# LSS_Pro_V0_2_BOTTOM.net
KiCad netlist of a schematic drawn in EAGLE
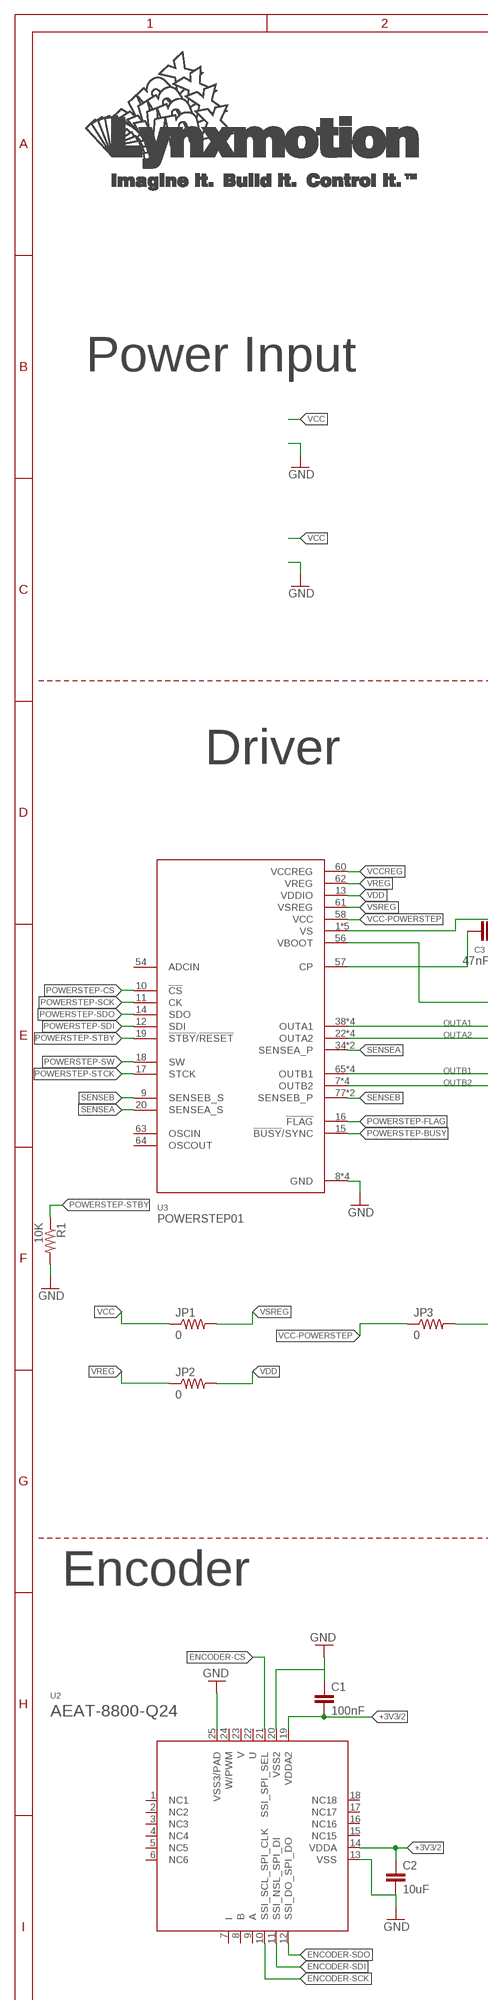
[diagram p0: schematic, sheet 1, part 1 of 2]
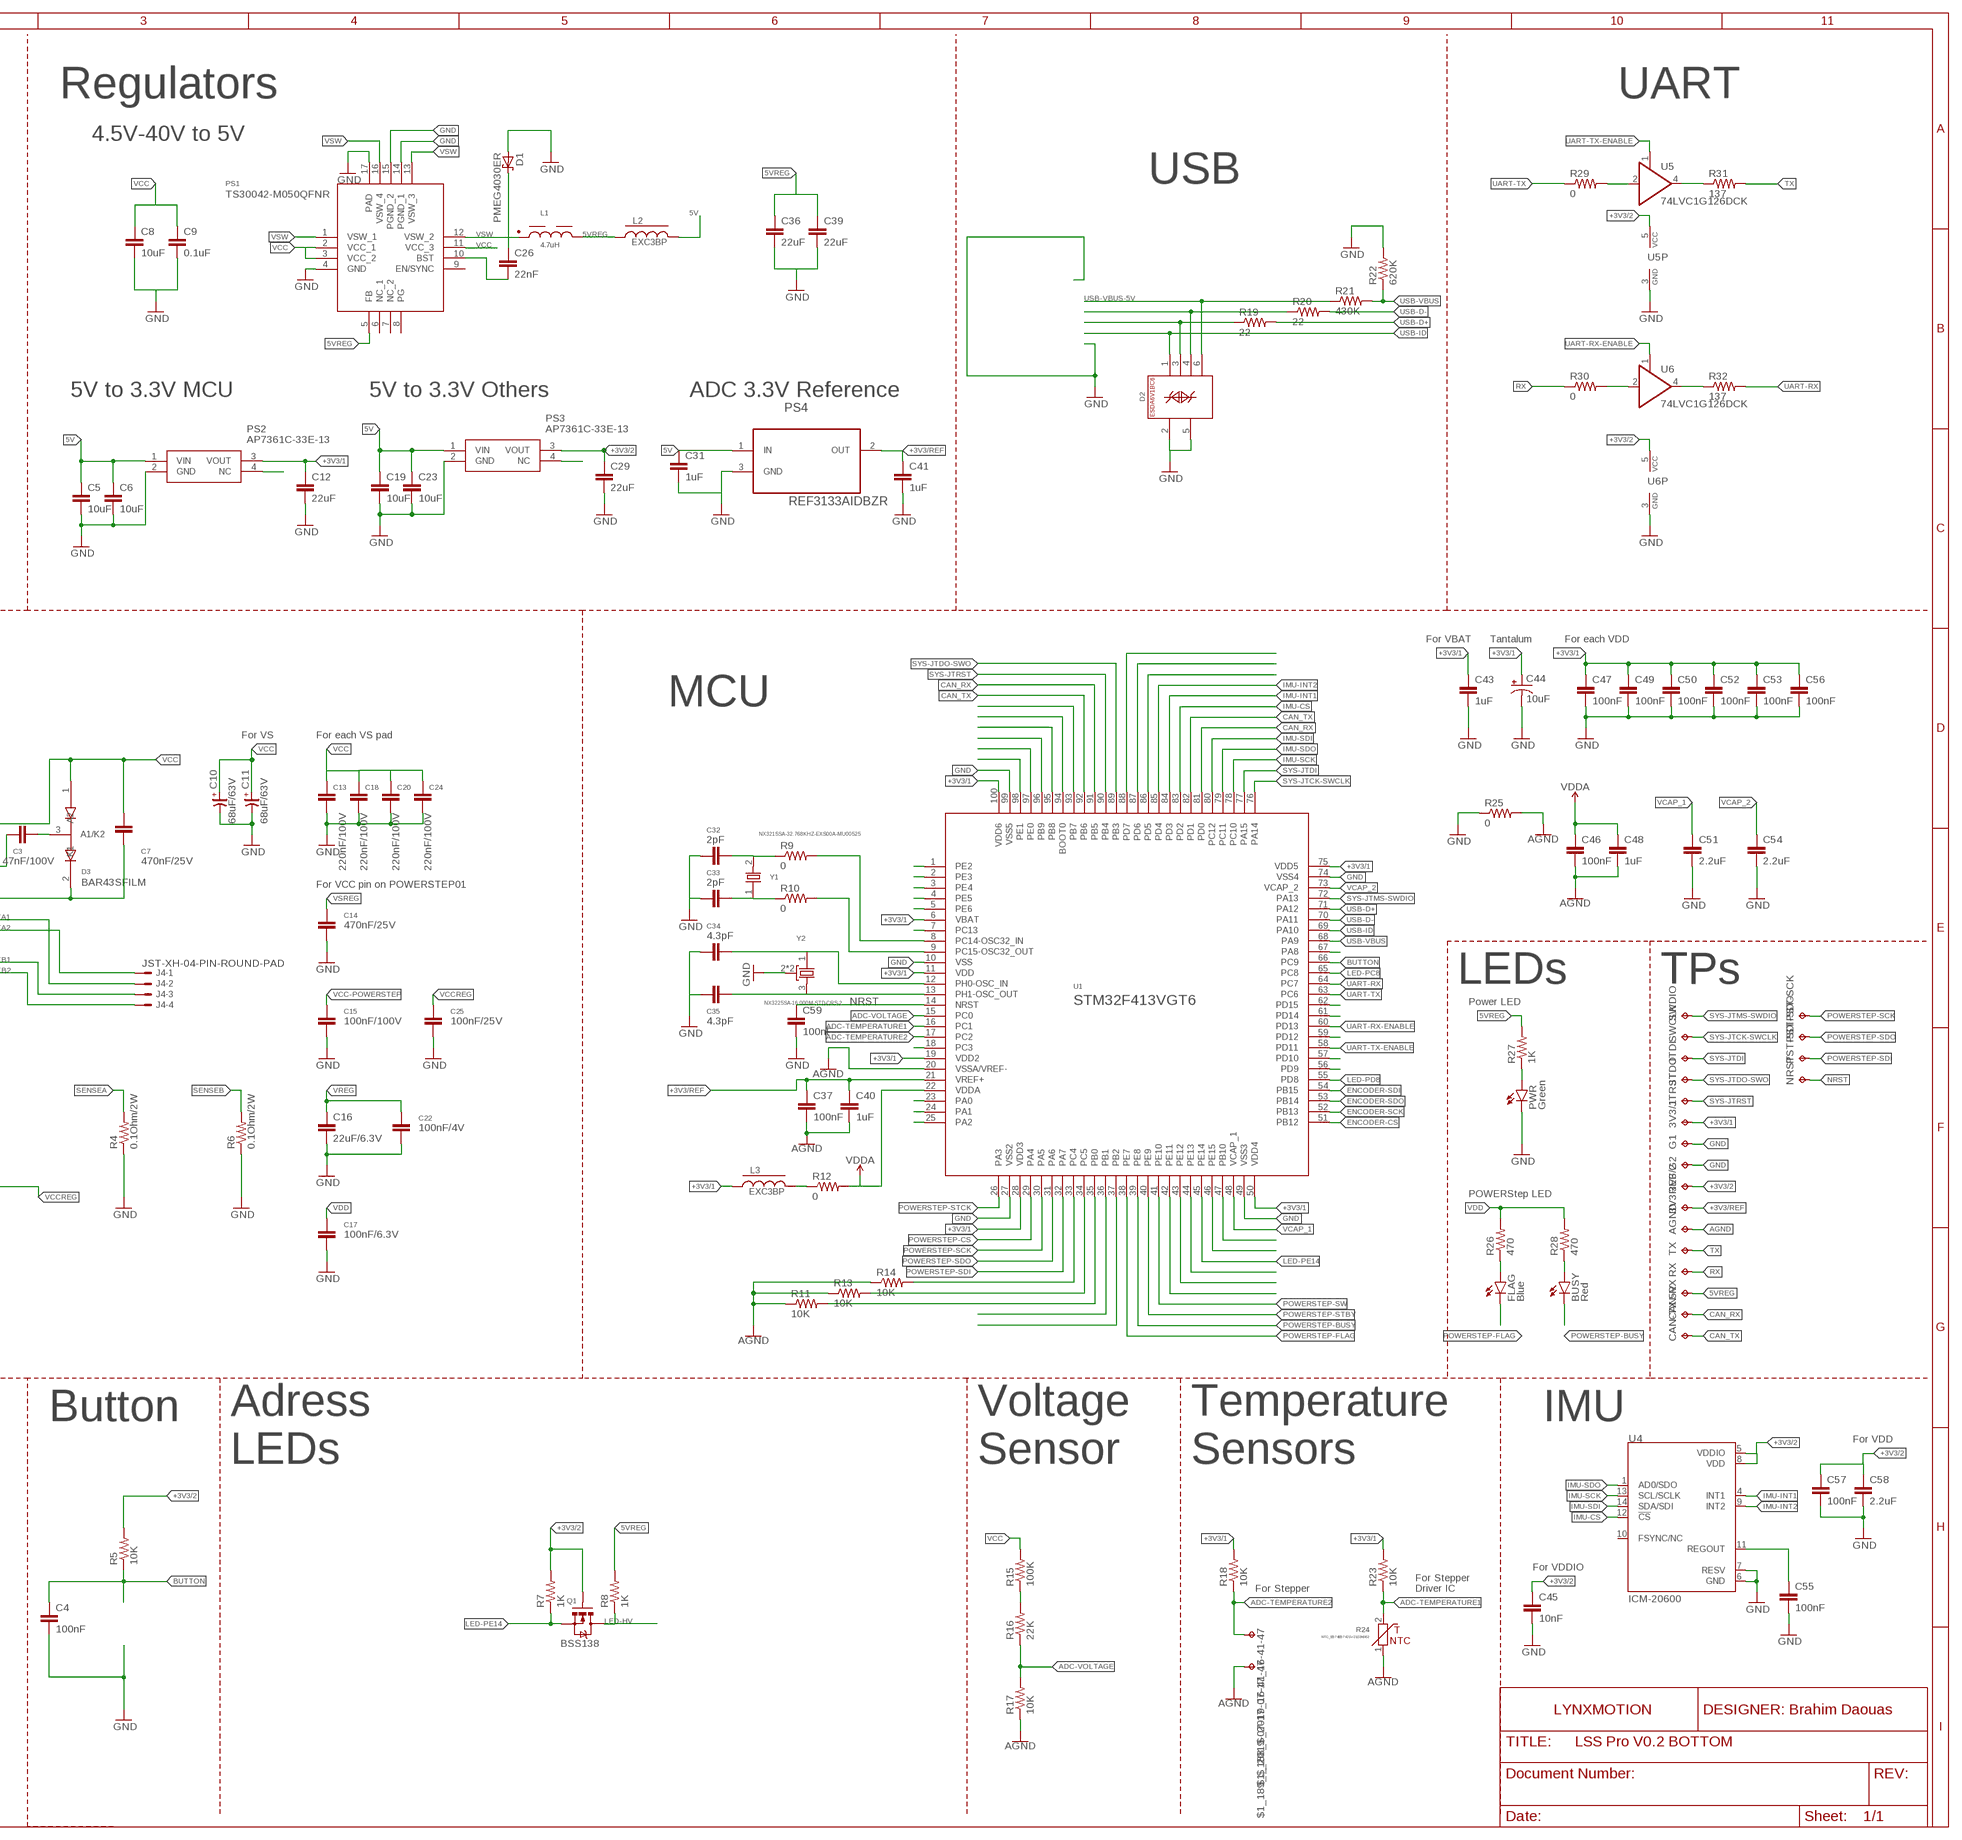
[diagram p1: schematic, sheet 1, part 2 of 2]

(export (version "E")
  (design (tool "Eeschema 10.0.6"))
  (components
    (comp (ref "$1_188_$_2019-07-17_16-41-47")
      (value "TP-040")
      (footprint "eagle-import:TP-040")
      (libsource (lib "eagle-import") (part "TP-040"))
    )
    (comp (ref "$1_189_$_2019-07-17_16-41-47")
      (value "TP-040")
      (footprint "eagle-import:TP-040")
      (libsource (lib "eagle-import") (part "TP-040"))
    )
    (comp (ref "3V3/1")
      (value "TPTP17R")
      (footprint "eagle-import:TP17R")
      (libsource (lib "eagle-import") (part "TPTP17R"))
    )
    (comp (ref "3V3/2")
      (value "TPTP17R")
      (footprint "eagle-import:TP17R")
      (libsource (lib "eagle-import") (part "TPTP17R"))
    )
    (comp (ref "3V3REF")
      (value "TPTP17R")
      (footprint "eagle-import:TP17R")
      (libsource (lib "eagle-import") (part "TPTP17R"))
    )
    (comp (ref "5V")
      (value "TPTP17R")
      (footprint "eagle-import:TP17R")
      (libsource (lib "eagle-import") (part "TPTP17R"))
    )
    (comp (ref "AGND")
      (value "TPTP17R")
      (footprint "eagle-import:TP17R")
      (libsource (lib "eagle-import") (part "TPTP17R"))
    )
    (comp (ref "BUSY")
      (value "Red")
      (footprint "eagle-import:LED-0603")
      (libsource (lib "eagle-import") (part "LED0603"))
    )
    (comp (ref "C1")
      (value "100nF")
      (footprint "eagle-import:0603-CAP")
      (libsource (lib "eagle-import") (part "CAP0603-CAP"))
    )
    (comp (ref "C2")
      (value "10uF")
      (footprint "eagle-import:0603-CAP")
      (libsource (lib "eagle-import") (part "CAP0603-CAP"))
    )
    (comp (ref "C3")
      (value "47nF/100V")
      (footprint "eagle-import:0805")
      (libsource (lib "eagle-import") (part "CAP0805"))
    )
    (comp (ref "C4")
      (value "100nF")
      (footprint "eagle-import:0603-CAP")
      (libsource (lib "eagle-import") (part "CAP0603-CAP"))
    )
    (comp (ref "C5")
      (value "10uF")
      (footprint "eagle-import:0805")
      (libsource (lib "eagle-import") (part "CAP0805"))
    )
    (comp (ref "C6")
      (value "10uF")
      (footprint "eagle-import:0805")
      (libsource (lib "eagle-import") (part "CAP0805"))
    )
    (comp (ref "C7")
      (value "470nF/25V")
      (footprint "eagle-import:0603-CAP")
      (libsource (lib "eagle-import") (part "CAP0603-CAP"))
    )
    (comp (ref "C8")
      (value "10uF")
      (footprint "eagle-import:1206")
      (libsource (lib "eagle-import") (part "CAP1206"))
    )
    (comp (ref "C9")
      (value "0.1uF")
      (footprint "eagle-import:0603-CAP")
      (libsource (lib "eagle-import") (part "CAP0603-CAP"))
    )
    (comp (ref "C10")
      (value "68uF/63V")
      (footprint "eagle-import:CSV-E_F")
      (libsource (lib "eagle-import") (part "CP_SV-E/F"))
    )
    (comp (ref "C11")
      (value "68uF/63V")
      (footprint "eagle-import:CSV-E_F")
      (libsource (lib "eagle-import") (part "CP_SV-E/F"))
    )
    (comp (ref "C12")
      (value "22uF")
      (footprint "eagle-import:0805")
      (libsource (lib "eagle-import") (part "CAP0805"))
    )
    (comp (ref "C13")
      (value "220nF/100V")
      (footprint "eagle-import:0805")
      (libsource (lib "eagle-import") (part "CAP0805"))
    )
    (comp (ref "C14")
      (value "470nF/25V")
      (footprint "eagle-import:0603-CAP")
      (libsource (lib "eagle-import") (part "CAP0603-CAP"))
    )
    (comp (ref "C15")
      (value "100nF/100V")
      (footprint "eagle-import:0603-CAP")
      (libsource (lib "eagle-import") (part "CAP0603-CAP"))
    )
    (comp (ref "C16")
      (value "22uF/6.3V")
      (footprint "eagle-import:1206")
      (libsource (lib "eagle-import") (part "CAP1206"))
    )
    (comp (ref "C17")
      (value "100nF/6.3V")
      (footprint "eagle-import:0603-CAP")
      (libsource (lib "eagle-import") (part "CAP0603-CAP"))
    )
    (comp (ref "C18")
      (value "220nF/100V")
      (footprint "eagle-import:0805")
      (libsource (lib "eagle-import") (part "CAP0805"))
    )
    (comp (ref "C19")
      (value "10uF")
      (footprint "eagle-import:0805")
      (libsource (lib "eagle-import") (part "CAP0805"))
    )
    (comp (ref "C20")
      (value "220nF/100V")
      (footprint "eagle-import:0805")
      (libsource (lib "eagle-import") (part "CAP0805"))
    )
    (comp (ref "C22")
      (value "100nF/4V")
      (footprint "eagle-import:0603-CAP")
      (libsource (lib "eagle-import") (part "CAP0603-CAP"))
    )
    (comp (ref "C23")
      (value "10uF")
      (footprint "eagle-import:0805")
      (libsource (lib "eagle-import") (part "CAP0805"))
    )
    (comp (ref "C24")
      (value "220nF/100V")
      (footprint "eagle-import:0805")
      (libsource (lib "eagle-import") (part "CAP0805"))
    )
    (comp (ref "C25")
      (value "100nF/25V")
      (footprint "eagle-import:0603-CAP")
      (libsource (lib "eagle-import") (part "CAP0603-CAP"))
    )
    (comp (ref "C26")
      (value "22nF")
      (footprint "eagle-import:0402-CAP")
      (libsource (lib "eagle-import") (part "CAP0402-CAP"))
    )
    (comp (ref "C29")
      (value "22uF")
      (footprint "eagle-import:0805")
      (libsource (lib "eagle-import") (part "CAP0805"))
    )
    (comp (ref "C31")
      (value "1uF")
      (footprint "eagle-import:0805")
      (libsource (lib "eagle-import") (part "CAP0805"))
    )
    (comp (ref "C32")
      (value "2pF")
      (footprint "eagle-import:0603-CAP")
      (libsource (lib "eagle-import") (part "CAP0603-CAP"))
    )
    (comp (ref "C33")
      (value "2pF")
      (footprint "eagle-import:0603-CAP")
      (libsource (lib "eagle-import") (part "CAP0603-CAP"))
    )
    (comp (ref "C34")
      (value "4.3pF")
      (footprint "eagle-import:0603-CAP")
      (libsource (lib "eagle-import") (part "CAP0603-CAP"))
    )
    (comp (ref "C35")
      (value "4.3pF")
      (footprint "eagle-import:0603-CAP")
      (libsource (lib "eagle-import") (part "CAP0603-CAP"))
    )
    (comp (ref "C36")
      (value "22uF")
      (footprint "eagle-import:0805")
      (libsource (lib "eagle-import") (part "CAP0805"))
    )
    (comp (ref "C37")
      (value "100nF")
      (footprint "eagle-import:0603-CAP")
      (libsource (lib "eagle-import") (part "CAP0603-CAP"))
    )
    (comp (ref "C39")
      (value "22uF")
      (footprint "eagle-import:0805")
      (libsource (lib "eagle-import") (part "CAP0805"))
    )
    (comp (ref "C40")
      (value "1uF")
      (footprint "eagle-import:0603-CAP")
      (libsource (lib "eagle-import") (part "CAP0603-CAP"))
    )
    (comp (ref "C41")
      (value "1uF")
      (footprint "eagle-import:0805")
      (libsource (lib "eagle-import") (part "CAP0805"))
    )
    (comp (ref "C43")
      (value "1uF")
      (footprint "eagle-import:0603-CAP")
      (libsource (lib "eagle-import") (part "CAP0603-CAP"))
    )
    (comp (ref "C44")
      (value "10uF")
      (footprint "eagle-import:EIA3216")
      (libsource (lib "eagle-import") (part "CAP_POL1206"))
    )
    (comp (ref "C45")
      (value "10nF")
      (footprint "eagle-import:0603-CAP")
      (libsource (lib "eagle-import") (part "CAP0603-CAP"))
    )
    (comp (ref "C46")
      (value "100nF")
      (footprint "eagle-import:0603-CAP")
      (libsource (lib "eagle-import") (part "CAP0603-CAP"))
    )
    (comp (ref "C47")
      (value "100nF")
      (footprint "eagle-import:0603-CAP")
      (libsource (lib "eagle-import") (part "CAP0603-CAP"))
    )
    (comp (ref "C48")
      (value "1uF")
      (footprint "eagle-import:0603-CAP")
      (libsource (lib "eagle-import") (part "CAP0603-CAP"))
    )
    (comp (ref "C49")
      (value "100nF")
      (footprint "eagle-import:0603-CAP")
      (libsource (lib "eagle-import") (part "CAP0603-CAP"))
    )
    (comp (ref "C50")
      (value "100nF")
      (footprint "eagle-import:0603-CAP")
      (libsource (lib "eagle-import") (part "CAP0603-CAP"))
    )
    (comp (ref "C51")
      (value "2.2uF")
      (footprint "eagle-import:1206")
      (libsource (lib "eagle-import") (part "CAP1206"))
    )
    (comp (ref "C52")
      (value "100nF")
      (footprint "eagle-import:0603-CAP")
      (libsource (lib "eagle-import") (part "CAP0603-CAP"))
    )
    (comp (ref "C53")
      (value "100nF")
      (footprint "eagle-import:0603-CAP")
      (libsource (lib "eagle-import") (part "CAP0603-CAP"))
    )
    (comp (ref "C54")
      (value "2.2uF")
      (footprint "eagle-import:1206")
      (libsource (lib "eagle-import") (part "CAP1206"))
    )
    (comp (ref "C55")
      (value "100nF")
      (footprint "eagle-import:0603-CAP")
      (libsource (lib "eagle-import") (part "CAP0603-CAP"))
    )
    (comp (ref "C56")
      (value "100nF")
      (footprint "eagle-import:0603-CAP")
      (libsource (lib "eagle-import") (part "CAP0603-CAP"))
    )
    (comp (ref "C57")
      (value "100nF")
      (footprint "eagle-import:0603-CAP")
      (libsource (lib "eagle-import") (part "CAP0603-CAP"))
    )
    (comp (ref "C58")
      (value "2.2uF")
      (footprint "eagle-import:1206")
      (libsource (lib "eagle-import") (part "CAP1206"))
    )
    (comp (ref "C59")
      (value "100nF")
      (footprint "eagle-import:0603-CAP")
      (libsource (lib "eagle-import") (part "CAP0603-CAP"))
    )
    (comp (ref "CAN-RX")
      (value "TPTP17R")
      (footprint "eagle-import:TP17R")
      (libsource (lib "eagle-import") (part "TPTP17R"))
    )
    (comp (ref "CAN-TX")
      (value "TPTP17R")
      (footprint "eagle-import:TP17R")
      (libsource (lib "eagle-import") (part "TPTP17R"))
    )
    (comp (ref "D1")
      (value "PMEG4030ER")
      (footprint "eagle-import:SOD123W")
      (libsource (lib "eagle-import") (part "PMEG4030ER"))
    )
    (comp (ref "D2")
      (value "ESDA6V1BC6")
      (footprint "eagle-import:SOT-23-6L")
      (libsource (lib "eagle-import") (part "ESDA6V1BC6"))
    )
    (comp (ref "D3")
      (value "BAR43SFILM")
      (footprint "eagle-import:SOT105P242X150-3N")
      (fields (field (name "MOUSER_PART_NUMBER") "511-BAR43SFILM") (field (name "RS_PART_NUMBER") "4384762"))
      (libsource (lib "eagle-import") (part "BAR43SFILM"))
    )
    (comp (ref "FLAG")
      (value "Blue")
      (footprint "eagle-import:LED-0603")
      (libsource (lib "eagle-import") (part "LED0603"))
    )
    (comp (ref "G1")
      (value "TPTP17R")
      (footprint "eagle-import:TP17R")
      (libsource (lib "eagle-import") (part "TPTP17R"))
    )
    (comp (ref "G2")
      (value "TPTP17R")
      (footprint "eagle-import:TP17R")
      (libsource (lib "eagle-import") (part "TPTP17R"))
    )
    (comp (ref "J4")
      (value "JST-XH-04-PIN-ROUND-PAD")
      (footprint "eagle-import:JST-XH-04-PACKAGE-ROUND-PAD")
      (libsource (lib "eagle-import") (part "JST-XH-04-PIN-ROUND-PAD"))
    )
    (comp (ref "JP1")
      (value "0")
      (footprint "eagle-import:0603-RES")
      (libsource (lib "eagle-import") (part "RESISTOR0603"))
    )
    (comp (ref "JP2")
      (value "0")
      (footprint "eagle-import:0603-RES")
      (libsource (lib "eagle-import") (part "RESISTOR0603"))
    )
    (comp (ref "JP3")
      (value "0")
      (footprint "eagle-import:0603-RES")
      (libsource (lib "eagle-import") (part "RESISTOR0603"))
    )
    (comp (ref "JTDI")
      (value "TPTP17R")
      (footprint "eagle-import:TP17R")
      (libsource (lib "eagle-import") (part "TPTP17R"))
    )
    (comp (ref "JTDO")
      (value "TPTP17R")
      (footprint "eagle-import:TP17R")
      (libsource (lib "eagle-import") (part "TPTP17R"))
    )
    (comp (ref "JTRST")
      (value "TPTP17R")
      (footprint "eagle-import:TP17R")
      (libsource (lib "eagle-import") (part "TPTP17R"))
    )
    (comp (ref "L1")
      (value "4.7uH")
      (footprint "eagle-import:WE-PD2_5848_5820")
      (libsource (lib "eagle-import") (part "WE-PD2_5848_744774047"))
    )
    (comp (ref "L2")
      (value "EXC3BP")
      (footprint "eagle-import:L0603")
      (libsource (lib "eagle-import") (part "EXC3BP"))
    )
    (comp (ref "L3")
      (value "EXC3BP")
      (footprint "eagle-import:L0603")
      (libsource (lib "eagle-import") (part "EXC3BP"))
    )
    (comp (ref "NRST")
      (value "TPTP17R")
      (footprint "eagle-import:TP17R")
      (libsource (lib "eagle-import") (part "TPTP17R"))
    )
    (comp (ref "PS1")
      (value "TS30042-M050QFNR")
      (footprint "eagle-import:QFN16")
      (libsource (lib "eagle-import") (part "TS30042-M050QFNR"))
    )
    (comp (ref "PS2")
      (value "AP7361C-33E-13")
      (footprint "eagle-import:SOT230P700X165-4N")
      (libsource (lib "eagle-import") (part "AP7361C-33E-13"))
    )
    (comp (ref "PS3")
      (value "AP7361C-33E-13")
      (footprint "eagle-import:SOT230P700X165-4N")
      (libsource (lib "eagle-import") (part "AP7361C-33E-13"))
    )
    (comp (ref "PS4")
      (value "REF3133AIDBZR")
      (footprint "eagle-import:SOT95P237X112-3N")
      (fields (field (name "MF") "Texas Instruments"))
      (libsource (lib "eagle-import") (part "REF3133AIDBZR"))
    )
    (comp (ref "PST-SCK")
      (value "TPTP17R")
      (footprint "eagle-import:TP17R")
      (libsource (lib "eagle-import") (part "TPTP17R"))
    )
    (comp (ref "PST-SDI")
      (value "TPTP17R")
      (footprint "eagle-import:TP17R")
      (libsource (lib "eagle-import") (part "TPTP17R"))
    )
    (comp (ref "PST-SDO")
      (value "TPTP17R")
      (footprint "eagle-import:TP17R")
      (libsource (lib "eagle-import") (part "TPTP17R"))
    )
    (comp (ref "PWR")
      (value "Green")
      (footprint "eagle-import:LED-0603")
      (libsource (lib "eagle-import") (part "LED0603"))
    )
    (comp (ref "Q1")
      (value "BSS138")
      (footprint "eagle-import:SOT23-3")
      (libsource (lib "eagle-import") (part "MOSFET-NCHANNELSMD"))
    )
    (comp (ref "R1")
      (value "10K")
      (footprint "eagle-import:0402-RES")
      (libsource (lib "eagle-import") (part "RESISTOR0402-RES"))
    )
    (comp (ref "R4")
      (value "0.1Ohm/2W")
      (footprint "eagle-import:R2512")
      (libsource (lib "eagle-import") (part "SparkFun-Resistors_RESISTOR2512"))
    )
    (comp (ref "R5")
      (value "10K")
      (footprint "eagle-import:0603-RES")
      (libsource (lib "eagle-import") (part "RESISTOR0603"))
    )
    (comp (ref "R6")
      (value "0.1Ohm/2W")
      (footprint "eagle-import:R2512")
      (libsource (lib "eagle-import") (part "SparkFun-Resistors_RESISTOR2512"))
    )
    (comp (ref "R7")
      (value "1K")
      (footprint "eagle-import:0603-RES")
      (libsource (lib "eagle-import") (part "SparkFun-Resistors_RESISTOR0603-RES"))
    )
    (comp (ref "R8")
      (value "1K")
      (footprint "eagle-import:0603-RES")
      (libsource (lib "eagle-import") (part "SparkFun-Resistors_RESISTOR0603-RES"))
    )
    (comp (ref "R9")
      (value "0")
      (footprint "eagle-import:0603-RES")
      (libsource (lib "eagle-import") (part "RESISTOR0603"))
    )
    (comp (ref "R10")
      (value "0")
      (footprint "eagle-import:0603-RES")
      (libsource (lib "eagle-import") (part "RESISTOR0603"))
    )
    (comp (ref "R11")
      (value "10K")
      (footprint "eagle-import:0402-RES")
      (libsource (lib "eagle-import") (part "RESISTOR0402-RES"))
    )
    (comp (ref "R12")
      (value "0")
      (footprint "eagle-import:0603-RES")
      (libsource (lib "eagle-import") (part "RESISTOR0603"))
    )
    (comp (ref "R13")
      (value "10K")
      (footprint "eagle-import:0402-RES")
      (libsource (lib "eagle-import") (part "RESISTOR0402-RES"))
    )
    (comp (ref "R14")
      (value "10K")
      (footprint "eagle-import:0402-RES")
      (libsource (lib "eagle-import") (part "RESISTOR0402-RES"))
    )
    (comp (ref "R15")
      (value "100K")
      (footprint "eagle-import:0603-RES")
      (libsource (lib "eagle-import") (part "SparkFun-Resistors_RESISTOR0603-RES"))
    )
    (comp (ref "R16")
      (value "22K")
      (footprint "eagle-import:0603-RES")
      (libsource (lib "eagle-import") (part "SparkFun-Resistors_RESISTOR0603-RES"))
    )
    (comp (ref "R17")
      (value "10K")
      (footprint "eagle-import:0603-RES")
      (libsource (lib "eagle-import") (part "SparkFun-Resistors_RESISTOR0603-RES"))
    )
    (comp (ref "R18")
      (value "10K")
      (footprint "eagle-import:0603-RES")
      (libsource (lib "eagle-import") (part "10KOHM-1/10W-1%(0603)0603"))
    )
    (comp (ref "R19")
      (value "22")
      (footprint "eagle-import:0603-RES")
      (libsource (lib "eagle-import") (part "RESISTOR0603"))
    )
    (comp (ref "R20")
      (value "22")
      (footprint "eagle-import:0603-RES")
      (libsource (lib "eagle-import") (part "RESISTOR0603"))
    )
    (comp (ref "R21")
      (value "430K")
      (footprint "eagle-import:0603-RES")
      (libsource (lib "eagle-import") (part "RESISTOR0603"))
    )
    (comp (ref "R22")
      (value "620K")
      (footprint "eagle-import:0603-RES")
      (libsource (lib "eagle-import") (part "RESISTOR0603"))
    )
    (comp (ref "R23")
      (value "10K")
      (footprint "eagle-import:0603-RES")
      (libsource (lib "eagle-import") (part "10KOHM-1/10W-1%(0603)0603"))
    )
    (comp (ref "R24")
      (value "NTC_B574B57421V2102H062")
      (footprint "eagle-import:R0805")
      (fields (field (name "MPN") "B57421V2102H062"))
      (libsource (lib "eagle-import") (part "NTC_B574B57421V2102H062"))
    )
    (comp (ref "R25")
      (value "0")
      (footprint "eagle-import:0603-RES")
      (libsource (lib "eagle-import") (part "RESISTOR0603"))
    )
    (comp (ref "R26")
      (value "470")
      (footprint "eagle-import:0402-RES")
      (libsource (lib "eagle-import") (part "RESISTOR0402-RES"))
    )
    (comp (ref "R27")
      (value "1K")
      (footprint "eagle-import:0402-RES")
      (libsource (lib "eagle-import") (part "RESISTOR0402-RES"))
    )
    (comp (ref "R28")
      (value "470")
      (footprint "eagle-import:0402-RES")
      (libsource (lib "eagle-import") (part "RESISTOR0402-RES"))
    )
    (comp (ref "R29")
      (value "0")
      (footprint "eagle-import:0603-RES")
      (libsource (lib "eagle-import") (part "RESISTOR0603"))
    )
    (comp (ref "R30")
      (value "0")
      (footprint "eagle-import:0603-RES")
      (libsource (lib "eagle-import") (part "RESISTOR0603"))
    )
    (comp (ref "R31")
      (value "137")
      (footprint "eagle-import:0603-RES")
      (libsource (lib "eagle-import") (part "RESISTOR0603"))
    )
    (comp (ref "R32")
      (value "137")
      (footprint "eagle-import:0603-RES")
      (libsource (lib "eagle-import") (part "RESISTOR0603"))
    )
    (comp (ref "RX")
      (value "TPTP17R")
      (footprint "eagle-import:TP17R")
      (libsource (lib "eagle-import") (part "TPTP17R"))
    )
    (comp (ref "SWCLK")
      (value "TPTP17R")
      (footprint "eagle-import:TP17R")
      (libsource (lib "eagle-import") (part "TPTP17R"))
    )
    (comp (ref "SWDIO")
      (value "TPTP17R")
      (footprint "eagle-import:TP17R")
      (libsource (lib "eagle-import") (part "TPTP17R"))
    )
    (comp (ref "TX")
      (value "TPTP17R")
      (footprint "eagle-import:TP17R")
      (libsource (lib "eagle-import") (part "TPTP17R"))
    )
    (comp (ref "U1")
      (value "STM32F413VGT6")
      (footprint "eagle-import:LQFP100")
      (libsource (lib "eagle-import") (part "STM32F413VGT6"))
    )
    (comp (ref "U2")
      (value "AEAT-8800-Q24")
      (footprint "eagle-import:QFN24")
      (libsource (lib "eagle-import") (part "AEAT-8800-Q24"))
    )
    (comp (ref "U3")
      (value "POWERSTEP01")
      (footprint "eagle-import:IC_POWERSTEP01")
      (fields (field (name "MF") "STMicroelectronics"))
      (libsource (lib "eagle-import") (part "POWERSTEP01"))
    )
    (comp (ref "U4")
      (value "ICM-20600")
      (footprint "eagle-import:PQFN50P250X300X97-14N")
      (fields (field (name "MF") "TDK InvenSense"))
      (libsource (lib "eagle-import") (part "ICM-20600"))
    )
    (comp (ref "U5")
      (value "74LVC1G126DCK")
      (footprint "eagle-import:SC70-5")
      (libsource (lib "eagle-import") (part "741G126DCKLVC"))
    )
    (comp (ref "U6")
      (value "74LVC1G126DCK")
      (footprint "eagle-import:SC70-5")
      (libsource (lib "eagle-import") (part "741G126DCKLVC"))
    )
    (comp (ref "Y1")
      (value "NX3215SA-32.768KHZ-EXS00A-MU00525")
      (footprint "eagle-import:NX3215SA")
      (fields
        (field (name "MANUFACTURER_PART_NUMBER") "NX3215SA-32.768K-STD-MUA-8")
        (field (name "MOUSER_PART_NUMBER") "344-NX3215SA32768K8")
        (field (name "RS_PART_NUMBER") "7537568")
      )
      (libsource (lib "eagle-import") (part "NX3215SA-32.768KHZ-EXS00A-MU00525"))
    )
    (comp (ref "Y2")
      (value "NX3225SA-16.000M-STD-CRS-2")
      (footprint "eagle-import:OSCCC320X250X60N")
      (fields (field (name "MF") "NDK America,") (field (name "MP") "NX3225SA-12.000M-STD-CRS-2"))
      (libsource (lib "eagle-import") (part "NX3225SA-16.000M-STD-CRS-2"))
    )
  )
  (nets
    (net (code "1") (name "+3V3{slash}1") (class "Default")
      (node (ref "3V3/1") (pin "TP") (pinfunction "TP_TP") (pintype "input"))
      (node (ref "C12") (pin "1") (pinfunction "1_1") (pintype "passive"))
      (node (ref "C43") (pin "1") (pinfunction "1_1") (pintype "passive"))
      (node (ref "C44") (pin "A") (pinfunction "+_A") (pintype "passive"))
      (node (ref "C47") (pin "1") (pinfunction "1_1") (pintype "passive"))
      (node (ref "C49") (pin "1") (pinfunction "1_1") (pintype "passive"))
      (node (ref "C50") (pin "1") (pinfunction "1_1") (pintype "passive"))
      (node (ref "C52") (pin "1") (pinfunction "1_1") (pintype "passive"))
      (node (ref "C53") (pin "1") (pinfunction "1_1") (pintype "passive"))
      (node (ref "C56") (pin "1") (pinfunction "1_1") (pintype "passive"))
      (node (ref "L3") (pin "1") (pinfunction "1_1") (pintype "passive"))
      (node (ref "PS2") (pin "3") (pinfunction "VOUT_3") (pintype "output"))
      (node (ref "R18") (pin "2") (pinfunction "2_2") (pintype "passive"))
      (node (ref "R23") (pin "2") (pinfunction "2_2") (pintype "passive"))
      (node (ref "U1") (pin "100") (pinfunction "VDD6_100") (pintype "power_in"))
      (node (ref "U1") (pin "11") (pinfunction "VDD_11") (pintype "power_in"))
      (node (ref "U1") (pin "19") (pinfunction "VDD2_19") (pintype "power_in"))
      (node (ref "U1") (pin "28") (pinfunction "VDD3_28") (pintype "power_in"))
      (node (ref "U1") (pin "50") (pinfunction "VDD4_50") (pintype "power_in"))
      (node (ref "U1") (pin "6") (pinfunction "VBAT_6") (pintype "power_in"))
      (node (ref "U1") (pin "75") (pinfunction "VDD5_75") (pintype "power_in"))
    )
    (net (code "2") (name "+3V3{slash}2") (class "Default")
      (node (ref "3V3/2") (pin "TP") (pinfunction "TP_TP") (pintype "input"))
      (node (ref "C1") (pin "2") (pinfunction "2_2") (pintype "passive"))
      (node (ref "C2") (pin "1") (pinfunction "1_1") (pintype "passive"))
      (node (ref "C29") (pin "1") (pinfunction "1_1") (pintype "passive"))
      (node (ref "C45") (pin "1") (pinfunction "1_1") (pintype "passive"))
      (node (ref "C57") (pin "1") (pinfunction "1_1") (pintype "passive"))
      (node (ref "C58") (pin "1") (pinfunction "1_1") (pintype "passive"))
      (node (ref "PS3") (pin "3") (pinfunction "VOUT_3") (pintype "output"))
      (node (ref "Q1") (pin "1") (pinfunction "G_1") (pintype "passive"))
      (node (ref "R5") (pin "2") (pinfunction "2_2") (pintype "passive"))
      (node (ref "R7") (pin "2") (pinfunction "2_2") (pintype "passive"))
      (node (ref "U2") (pin "14") (pinfunction "VDDA_14") (pintype "power_in"))
      (node (ref "U2") (pin "19") (pinfunction "VDDA2_19") (pintype "power_in"))
      (node (ref "U4") (pin "5") (pinfunction "VDDIO_5") (pintype "power_in"))
      (node (ref "U4") (pin "8") (pinfunction "VDD_8") (pintype "power_in"))
      (node (ref "U5") (pin "5") (pinfunction "VCC_5") (pintype "power_in"))
      (node (ref "U6") (pin "5") (pinfunction "VCC_5") (pintype "power_in"))
    )
    (net (code "3") (name "+3V3{slash}REF") (class "Default")
      (node (ref "3V3REF") (pin "TP") (pinfunction "TP_TP") (pintype "input"))
      (node (ref "C37") (pin "1") (pinfunction "1_1") (pintype "passive"))
      (node (ref "C40") (pin "1") (pinfunction "1_1") (pintype "passive"))
      (node (ref "C41") (pin "1") (pinfunction "1_1") (pintype "passive"))
      (node (ref "PS4") (pin "2") (pinfunction "OUT_2") (pintype "output"))
      (node (ref "U1") (pin "21") (pinfunction "VREF+_21") (pintype "power_in"))
    )
    (net (code "4") (name "/LED-HV") (class "Default")
      (node (ref "Q1") (pin "3") (pinfunction "D_3") (pintype "passive"))
      (node (ref "R8") (pin "1") (pinfunction "1_1") (pintype "passive"))
    )
    (net (code "5") (name "/OUTA1") (class "Default")
      (node (ref "J4") (pin "2") (pinfunction "S_2") (pintype "passive"))
      (node (ref "U3") (pin "38") (pinfunction "OUTA1_38") (pintype "output"))
      (node (ref "U3") (pin "42") (pinfunction "OUTA1_42") (pintype "output"))
      (node (ref "U3") (pin "53") (pinfunction "OUTA1_53") (pintype "output"))
      (node (ref "U3") (pin "EPAD4") (pinfunction "OUTA1_EPAD4") (pintype "output"))
    )
    (net (code "6") (name "/OUTA2") (class "Default")
      (node (ref "J4") (pin "1") (pinfunction "S_1") (pintype "passive"))
      (node (ref "U3") (pin "22") (pinfunction "OUTA2_22") (pintype "output"))
      (node (ref "U3") (pin "33") (pinfunction "OUTA2_33") (pintype "output"))
      (node (ref "U3") (pin "37") (pinfunction "OUTA2_37") (pintype "output"))
      (node (ref "U3") (pin "EPAD3") (pinfunction "OUTA2_EPAD3") (pintype "output"))
    )
    (net (code "7") (name "/OUTB1") (class "Default")
      (node (ref "J4") (pin "3") (pinfunction "S_3") (pintype "passive"))
      (node (ref "U3") (pin "65") (pinfunction "OUTB1_65") (pintype "output"))
      (node (ref "U3") (pin "76") (pinfunction "OUTB1_76") (pintype "output"))
      (node (ref "U3") (pin "80") (pinfunction "OUTB1_80") (pintype "output"))
      (node (ref "U3") (pin "EPAD7") (pinfunction "OUTB1_EPAD7") (pintype "output"))
    )
    (net (code "8") (name "/OUTB2") (class "Default")
      (node (ref "J4") (pin "4") (pinfunction "S_4") (pintype "passive"))
      (node (ref "U3") (pin "7") (pinfunction "OUTB2_7") (pintype "output"))
      (node (ref "U3") (pin "81") (pinfunction "OUTB2_81") (pintype "output"))
      (node (ref "U3") (pin "85") (pinfunction "OUTB2_85") (pintype "output"))
      (node (ref "U3") (pin "EPAD8") (pinfunction "OUTB2_EPAD8") (pintype "output"))
    )
    (net (code "9") (name "/USB-VBUS-5V") (class "Default")
      (node (ref "D2") (pin "6") (pinfunction "6_6") (pintype "bidirectional"))
      (node (ref "R21") (pin "1") (pinfunction "1_1") (pintype "passive"))
    )
    (net (code "10") (name "5V") (class "Default")
      (node (ref "C19") (pin "1") (pinfunction "1_1") (pintype "passive"))
      (node (ref "C23") (pin "1") (pinfunction "1_1") (pintype "passive"))
      (node (ref "C31") (pin "1") (pinfunction "1_1") (pintype "passive"))
      (node (ref "C5") (pin "1") (pinfunction "1_1") (pintype "passive"))
      (node (ref "C6") (pin "1") (pinfunction "1_1") (pintype "passive"))
      (node (ref "L2") (pin "2") (pinfunction "2_2") (pintype "passive"))
      (node (ref "PS2") (pin "1") (pinfunction "VIN_1") (pintype "input"))
      (node (ref "PS3") (pin "1") (pinfunction "VIN_1") (pintype "input"))
      (node (ref "PS4") (pin "1") (pinfunction "IN_1") (pintype "power_in"))
    )
    (net (code "11") (name "5VREG") (class "Default")
      (node (ref "5V") (pin "TP") (pinfunction "TP_TP") (pintype "input"))
      (node (ref "C36") (pin "1") (pinfunction "1_1") (pintype "passive"))
      (node (ref "C39") (pin "1") (pinfunction "1_1") (pintype "passive"))
      (node (ref "L1") (pin "2") (pinfunction "2_2") (pintype "passive"))
      (node (ref "L2") (pin "1") (pinfunction "1_1") (pintype "passive"))
      (node (ref "PS1") (pin "5") (pinfunction "FB_5") (pintype "bidirectional"))
      (node (ref "R27") (pin "2") (pinfunction "2_2") (pintype "passive"))
      (node (ref "R8") (pin "2") (pinfunction "2_2") (pintype "passive"))
    )
    (net (code "12") (name "ADC-TEMPERATURE1") (class "Default")
      (node (ref "R23") (pin "1") (pinfunction "1_1") (pintype "passive"))
      (node (ref "R24") (pin "2") (pinfunction "P$2_2") (pintype "passive"))
      (node (ref "U1") (pin "16") (pinfunction "PC1_16") (pintype "bidirectional"))
    )
    (net (code "13") (name "ADC-TEMPERATURE2") (class "Default")
      (node (ref "$1_188_$_2019-07-17_16-41-47") (pin "1") (pinfunction "1_1") (pintype "passive"))
      (node (ref "R18") (pin "1") (pinfunction "1_1") (pintype "passive"))
      (node (ref "U1") (pin "17") (pinfunction "PC2_17") (pintype "bidirectional"))
    )
    (net (code "14") (name "ADC-VOLTAGE") (class "Default")
      (node (ref "R16") (pin "1") (pinfunction "1_1") (pintype "passive"))
      (node (ref "R17") (pin "2") (pinfunction "2_2") (pintype "passive"))
      (node (ref "U1") (pin "15") (pinfunction "PC0_15") (pintype "bidirectional"))
    )
    (net (code "15") (name "AGND") (class "Default")
      (node (ref "$1_189_$_2019-07-17_16-41-47") (pin "1") (pinfunction "1_1") (pintype "passive"))
      (node (ref "AGND") (pin "TP") (pinfunction "TP_TP") (pintype "input"))
      (node (ref "C37") (pin "2") (pinfunction "2_2") (pintype "passive"))
      (node (ref "C40") (pin "2") (pinfunction "2_2") (pintype "passive"))
      (node (ref "C46") (pin "2") (pinfunction "2_2") (pintype "passive"))
      (node (ref "C48") (pin "2") (pinfunction "2_2") (pintype "passive"))
      (node (ref "R11") (pin "1") (pinfunction "1_1") (pintype "passive"))
      (node (ref "R13") (pin "1") (pinfunction "1_1") (pintype "passive"))
      (node (ref "R14") (pin "1") (pinfunction "1_1") (pintype "passive"))
      (node (ref "R17") (pin "1") (pinfunction "1_1") (pintype "passive"))
      (node (ref "R24") (pin "1") (pinfunction "P$1_1") (pintype "passive"))
      (node (ref "R25") (pin "2") (pinfunction "2_2") (pintype "passive"))
      (node (ref "U1") (pin "20") (pinfunction "VSSA/VREF-_20") (pintype "power_in"))
    )
    (net (code "16") (name "BUTTON") (class "Default")
      (node (ref "C4") (pin "1") (pinfunction "1_1") (pintype "passive"))
      (node (ref "R5") (pin "1") (pinfunction "1_1") (pintype "passive"))
      (node (ref "U1") (pin "66") (pinfunction "PC9_66") (pintype "bidirectional"))
    )
    (net (code "17") (name "CAN_RX") (class "Default")
      (node (ref "CAN-RX") (pin "TP") (pinfunction "TP_TP") (pintype "input"))
      (node (ref "U1") (pin "81") (pinfunction "PD0_81") (pintype "bidirectional"))
      (node (ref "U1") (pin "91") (pinfunction "PB5_91") (pintype "bidirectional"))
    )
    (net (code "18") (name "CAN_TX") (class "Default")
      (node (ref "CAN-TX") (pin "TP") (pinfunction "TP_TP") (pintype "input"))
      (node (ref "U1") (pin "82") (pinfunction "PD1_82") (pintype "bidirectional"))
      (node (ref "U1") (pin "92") (pinfunction "PB6_92") (pintype "bidirectional"))
    )
    (net (code "19") (name "ENCODER-CS") (class "Default")
      (node (ref "U1") (pin "51") (pinfunction "PB12_51") (pintype "bidirectional"))
      (node (ref "U2") (pin "21") (pinfunction "SSI_SPI_SEL_21") (pintype "input"))
    )
    (net (code "20") (name "ENCODER-SCK") (class "Default")
      (node (ref "U1") (pin "52") (pinfunction "PB13_52") (pintype "bidirectional"))
      (node (ref "U2") (pin "10") (pinfunction "SSI_SCL_SPI_CLK_10") (pintype "input"))
    )
    (net (code "21") (name "ENCODER-SDI") (class "Default")
      (node (ref "U1") (pin "54") (pinfunction "PB15_54") (pintype "bidirectional"))
      (node (ref "U2") (pin "11") (pinfunction "SSI_NSL_SPI_DI_11") (pintype "input"))
    )
    (net (code "22") (name "ENCODER-SDO") (class "Default")
      (node (ref "U1") (pin "53") (pinfunction "PB14_53") (pintype "bidirectional"))
      (node (ref "U2") (pin "12") (pinfunction "SSI_DO_SPI_DO_12") (pintype "output"))
    )
    (net (code "23") (name "GND") (class "Default")
      (node (ref "C1") (pin "1") (pinfunction "1_1") (pintype "passive"))
      (node (ref "C10") (pin "-") (pinfunction "-_-") (pintype "passive"))
      (node (ref "C11") (pin "-") (pinfunction "-_-") (pintype "passive"))
      (node (ref "C12") (pin "2") (pinfunction "2_2") (pintype "passive"))
      (node (ref "C13") (pin "2") (pinfunction "2_2") (pintype "passive"))
      (node (ref "C14") (pin "2") (pinfunction "2_2") (pintype "passive"))
      (node (ref "C15") (pin "2") (pinfunction "2_2") (pintype "passive"))
      (node (ref "C16") (pin "2") (pinfunction "2_2") (pintype "passive"))
      (node (ref "C17") (pin "2") (pinfunction "2_2") (pintype "passive"))
      (node (ref "C18") (pin "2") (pinfunction "2_2") (pintype "passive"))
      (node (ref "C19") (pin "2") (pinfunction "2_2") (pintype "passive"))
      (node (ref "C2") (pin "2") (pinfunction "2_2") (pintype "passive"))
      (node (ref "C20") (pin "2") (pinfunction "2_2") (pintype "passive"))
      (node (ref "C22") (pin "2") (pinfunction "2_2") (pintype "passive"))
      (node (ref "C23") (pin "2") (pinfunction "2_2") (pintype "passive"))
      (node (ref "C24") (pin "2") (pinfunction "2_2") (pintype "passive"))
      (node (ref "C25") (pin "2") (pinfunction "2_2") (pintype "passive"))
      (node (ref "C29") (pin "2") (pinfunction "2_2") (pintype "passive"))
      (node (ref "C31") (pin "2") (pinfunction "2_2") (pintype "passive"))
      (node (ref "C32") (pin "2") (pinfunction "2_2") (pintype "passive"))
      (node (ref "C33") (pin "2") (pinfunction "2_2") (pintype "passive"))
      (node (ref "C34") (pin "2") (pinfunction "2_2") (pintype "passive"))
      (node (ref "C35") (pin "2") (pinfunction "2_2") (pintype "passive"))
      (node (ref "C36") (pin "2") (pinfunction "2_2") (pintype "passive"))
      (node (ref "C39") (pin "2") (pinfunction "2_2") (pintype "passive"))
      (node (ref "C4") (pin "2") (pinfunction "2_2") (pintype "passive"))
      (node (ref "C41") (pin "2") (pinfunction "2_2") (pintype "passive"))
      (node (ref "C43") (pin "2") (pinfunction "2_2") (pintype "passive"))
      (node (ref "C44") (pin "C") (pinfunction "-_C") (pintype "passive"))
      (node (ref "C45") (pin "2") (pinfunction "2_2") (pintype "passive"))
      (node (ref "C47") (pin "2") (pinfunction "2_2") (pintype "passive"))
      (node (ref "C49") (pin "2") (pinfunction "2_2") (pintype "passive"))
      (node (ref "C5") (pin "2") (pinfunction "2_2") (pintype "passive"))
      (node (ref "C50") (pin "2") (pinfunction "2_2") (pintype "passive"))
      (node (ref "C51") (pin "2") (pinfunction "2_2") (pintype "passive"))
      (node (ref "C52") (pin "2") (pinfunction "2_2") (pintype "passive"))
      (node (ref "C53") (pin "2") (pinfunction "2_2") (pintype "passive"))
      (node (ref "C54") (pin "2") (pinfunction "2_2") (pintype "passive"))
      (node (ref "C55") (pin "2") (pinfunction "2_2") (pintype "passive"))
      (node (ref "C56") (pin "2") (pinfunction "2_2") (pintype "passive"))
      (node (ref "C57") (pin "2") (pinfunction "2_2") (pintype "passive"))
      (node (ref "C58") (pin "2") (pinfunction "2_2") (pintype "passive"))
      (node (ref "C59") (pin "2") (pinfunction "2_2") (pintype "passive"))
      (node (ref "C6") (pin "2") (pinfunction "2_2") (pintype "passive"))
      (node (ref "C8") (pin "2") (pinfunction "2_2") (pintype "passive"))
      (node (ref "C9") (pin "2") (pinfunction "2_2") (pintype "passive"))
      (node (ref "D1") (pin "2") (pinfunction "A_2") (pintype "passive"))
      (node (ref "D2") (pin "2") (pinfunction "2_2") (pintype "bidirectional"))
      (node (ref "D2") (pin "5") (pinfunction "5_5") (pintype "bidirectional"))
      (node (ref "G1") (pin "TP") (pinfunction "TP_TP") (pintype "input"))
      (node (ref "G2") (pin "TP") (pinfunction "TP_TP") (pintype "input"))
      (node (ref "PS1") (pin "14") (pinfunction "PGND_1_14") (pintype "bidirectional"))
      (node (ref "PS1") (pin "15") (pinfunction "PGND_2_15") (pintype "bidirectional"))
      (node (ref "PS1") (pin "17") (pinfunction "PAD_17") (pintype "bidirectional"))
      (node (ref "PS1") (pin "4") (pinfunction "GND_4") (pintype "bidirectional"))
      (node (ref "PS2") (pin "2") (pinfunction "GND_2") (pintype "power_in"))
      (node (ref "PS3") (pin "2") (pinfunction "GND_2") (pintype "power_in"))
      (node (ref "PS4") (pin "3") (pinfunction "GND_3") (pintype "passive"))
      (node (ref "PWR") (pin "C") (pinfunction "C_C") (pintype "passive"))
      (node (ref "R1") (pin "2") (pinfunction "2_2") (pintype "passive"))
      (node (ref "R22") (pin "2") (pinfunction "2_2") (pintype "passive"))
      (node (ref "R25") (pin "1") (pinfunction "1_1") (pintype "passive"))
      (node (ref "R4") (pin "1") (pinfunction "1_1") (pintype "passive"))
      (node (ref "R6") (pin "1") (pinfunction "1_1") (pintype "passive"))
      (node (ref "U1") (pin "10") (pinfunction "VSS_10") (pintype "power_in"))
      (node (ref "U1") (pin "27") (pinfunction "VSS2_27") (pintype "power_in"))
      (node (ref "U1") (pin "49") (pinfunction "VSS3_49") (pintype "power_in"))
      (node (ref "U1") (pin "74") (pinfunction "VSS4_74") (pintype "power_in"))
      (node (ref "U1") (pin "99") (pinfunction "VSS5_99") (pintype "power_in"))
      (node (ref "U2") (pin "13") (pinfunction "VSS_13") (pintype "power_in"))
      (node (ref "U2") (pin "20") (pinfunction "VSS2_20") (pintype "power_in"))
      (node (ref "U2") (pin "25") (pinfunction "VSS3/PAD_25") (pintype "power_in"))
      (node (ref "U3") (pin "21") (pinfunction "GND_21") (pintype "output"))
      (node (ref "U3") (pin "59") (pinfunction "GND_59") (pintype "output"))
      (node (ref "U3") (pin "8") (pinfunction "GND_8") (pintype "output"))
      (node (ref "U3") (pin "EPAD9") (pinfunction "GND_EPAD9") (pintype "output"))
      (node (ref "U4") (pin "6") (pinfunction "GND_6") (pintype "power_in"))
      (node (ref "U4") (pin "7") (pinfunction "RESV_7") (pintype "power_in"))
      (node (ref "U5") (pin "3") (pinfunction "GND_3") (pintype "power_in"))
      (node (ref "U6") (pin "3") (pinfunction "GND_3") (pintype "power_in"))
      (node (ref "Y2") (pin "2") (pinfunction "GND_2") (pintype "passive"))
      (node (ref "Y2") (pin "4") (pinfunction "GND_4") (pintype "passive"))
    )
    (net (code "24") (name "IMU-CS") (class "Default")
      (node (ref "U1") (pin "83") (pinfunction "PD2_83") (pintype "bidirectional"))
      (node (ref "U4") (pin "12") (pinfunction "~{CS}_12") (pintype "input"))
    )
    (net (code "25") (name "IMU-INT1") (class "Default")
      (node (ref "U1") (pin "84") (pinfunction "PD3_84") (pintype "bidirectional"))
      (node (ref "U4") (pin "4") (pinfunction "INT1_4") (pintype "output"))
    )
    (net (code "26") (name "IMU-INT2") (class "Default")
      (node (ref "U1") (pin "85") (pinfunction "PD4_85") (pintype "bidirectional"))
      (node (ref "U4") (pin "9") (pinfunction "INT2_9") (pintype "output"))
    )
    (net (code "27") (name "IMU-SCK") (class "Default")
      (node (ref "U1") (pin "78") (pinfunction "PC10_78") (pintype "bidirectional"))
      (node (ref "U4") (pin "13") (pinfunction "SCL/SCLK_13") (pintype "bidirectional"))
    )
    (net (code "28") (name "IMU-SDI") (class "Default")
      (node (ref "U1") (pin "80") (pinfunction "PC12_80") (pintype "bidirectional"))
      (node (ref "U4") (pin "14") (pinfunction "SDA/SDI_14") (pintype "bidirectional"))
    )
    (net (code "29") (name "IMU-SDO") (class "Default")
      (node (ref "U1") (pin "79") (pinfunction "PC11_79") (pintype "bidirectional"))
      (node (ref "U4") (pin "1") (pinfunction "AD0/SDO_1") (pintype "output"))
    )
    (net (code "30") (name "LED-PC8") (class "Default")
      (node (ref "U1") (pin "65") (pinfunction "PC8_65") (pintype "bidirectional"))
    )
    (net (code "31") (name "LED-PD8") (class "Default")
      (node (ref "U1") (pin "55") (pinfunction "PD8_55") (pintype "bidirectional"))
    )
    (net (code "32") (name "LED-PE14") (class "Default")
      (node (ref "Q1") (pin "2") (pinfunction "S_2") (pintype "passive"))
      (node (ref "R7") (pin "1") (pinfunction "1_1") (pintype "passive"))
      (node (ref "U1") (pin "45") (pinfunction "PE14_45") (pintype "bidirectional"))
    )
    (net (code "33") (name "NRST") (class "Default")
      (node (ref "C59") (pin "1") (pinfunction "1_1") (pintype "passive"))
      (node (ref "NRST") (pin "TP") (pinfunction "TP_TP") (pintype "input"))
      (node (ref "U1") (pin "14") (pinfunction "NRST_14") (pintype "bidirectional"))
    )
    (net (code "34") (name "Net-(BUSY-PadA)") (class "Default")
      (node (ref "BUSY") (pin "A") (pinfunction "A_A") (pintype "passive"))
      (node (ref "R28") (pin "1") (pinfunction "1_1") (pintype "passive"))
    )
    (net (code "35") (name "Net-(C32-Pad1)") (class "Default")
      (node (ref "C32") (pin "1") (pinfunction "1_1") (pintype "passive"))
      (node (ref "R9") (pin "1") (pinfunction "1_1") (pintype "passive"))
      (node (ref "Y1") (pin "2") (pinfunction "2_2") (pintype "bidirectional"))
    )
    (net (code "36") (name "Net-(C33-Pad1)") (class "Default")
      (node (ref "C33") (pin "1") (pinfunction "1_1") (pintype "passive"))
      (node (ref "R10") (pin "1") (pinfunction "1_1") (pintype "passive"))
      (node (ref "Y1") (pin "1") (pinfunction "1_1") (pintype "bidirectional"))
    )
    (net (code "37") (name "Net-(D2-Pad3)") (class "Default")
      (node (ref "D2") (pin "3") (pinfunction "3_3") (pintype "bidirectional"))
      (node (ref "R19") (pin "1") (pinfunction "1_1") (pintype "passive"))
    )
    (net (code "38") (name "Net-(D2-Pad4)") (class "Default")
      (node (ref "D2") (pin "4") (pinfunction "4_4") (pintype "bidirectional"))
      (node (ref "R20") (pin "1") (pinfunction "1_1") (pintype "passive"))
    )
    (net (code "39") (name "Net-(D3-A1{slash}K2)") (class "Default")
      (node (ref "C3") (pin "2") (pinfunction "2_2") (pintype "passive"))
      (node (ref "D3") (pin "3") (pinfunction "A1/K2_3") (pintype "bidirectional"))
    )
    (net (code "40") (name "Net-(D3-K1)") (class "Default")
      (node (ref "C7") (pin "2") (pinfunction "2_2") (pintype "passive"))
      (node (ref "D3") (pin "2") (pinfunction "K1_2") (pintype "bidirectional"))
      (node (ref "U3") (pin "56") (pinfunction "VBOOT_56") (pintype "power_in"))
    )
    (net (code "41") (name "Net-(FLAG-PadA)") (class "Default")
      (node (ref "FLAG") (pin "A") (pinfunction "A_A") (pintype "passive"))
      (node (ref "R26") (pin "1") (pinfunction "1_1") (pintype "passive"))
    )
    (net (code "42") (name "Net-(L3-Pad2)") (class "Default")
      (node (ref "L3") (pin "2") (pinfunction "2_2") (pintype "passive"))
      (node (ref "R12") (pin "1") (pinfunction "1_1") (pintype "passive"))
    )
    (net (code "43") (name "Net-(PS1-BST)") (class "Default")
      (node (ref "C26") (pin "2") (pinfunction "2_2") (pintype "passive"))
      (node (ref "PS1") (pin "10") (pinfunction "BST_10") (pintype "bidirectional"))
    )
    (net (code "44") (name "Net-(PWR-PadA)") (class "Default")
      (node (ref "PWR") (pin "A") (pinfunction "A_A") (pintype "passive"))
      (node (ref "R27") (pin "1") (pinfunction "1_1") (pintype "passive"))
    )
    (net (code "45") (name "Net-(R15-Pad1)") (class "Default")
      (node (ref "R15") (pin "1") (pinfunction "1_1") (pintype "passive"))
      (node (ref "R16") (pin "2") (pinfunction "2_2") (pintype "passive"))
    )
    (net (code "46") (name "Net-(U1-PB0)") (class "Default")
      (node (ref "R11") (pin "2") (pinfunction "2_2") (pintype "passive"))
      (node (ref "U1") (pin "35") (pinfunction "PB0_35") (pintype "bidirectional"))
    )
    (net (code "47") (name "Net-(U1-PC4)") (class "Default")
      (node (ref "R14") (pin "2") (pinfunction "2_2") (pintype "passive"))
      (node (ref "U1") (pin "33") (pinfunction "PC4_33") (pintype "bidirectional"))
    )
    (net (code "48") (name "Net-(U1-PC5)") (class "Default")
      (node (ref "R13") (pin "2") (pinfunction "2_2") (pintype "passive"))
      (node (ref "U1") (pin "34") (pinfunction "PC5_34") (pintype "bidirectional"))
    )
    (net (code "49") (name "Net-(U1-PC14-OSC32_IN)") (class "Default")
      (node (ref "R9") (pin "2") (pinfunction "2_2") (pintype "passive"))
      (node (ref "U1") (pin "8") (pinfunction "PC14-OSC32_IN_8") (pintype "bidirectional"))
    )
    (net (code "50") (name "Net-(U1-PC15-OSC32_OUT)") (class "Default")
      (node (ref "R10") (pin "2") (pinfunction "2_2") (pintype "passive"))
      (node (ref "U1") (pin "9") (pinfunction "PC15-OSC32_OUT_9") (pintype "bidirectional"))
    )
    (net (code "51") (name "Net-(U1-PH0-OSC_IN)") (class "Default")
      (node (ref "C34") (pin "1") (pinfunction "1_1") (pintype "passive"))
      (node (ref "U1") (pin "12") (pinfunction "PH0-OSC_IN_12") (pintype "bidirectional"))
      (node (ref "Y2") (pin "1") (pinfunction "1_1") (pintype "passive"))
    )
    (net (code "52") (name "Net-(U1-PH1-OSC_OUT)") (class "Default")
      (node (ref "C35") (pin "1") (pinfunction "1_1") (pintype "passive"))
      (node (ref "U1") (pin "13") (pinfunction "PH1-OSC_OUT_13") (pintype "bidirectional"))
      (node (ref "Y2") (pin "3") (pinfunction "3_3") (pintype "passive"))
    )
    (net (code "53") (name "Net-(U3-CP)") (class "Default")
      (node (ref "C3") (pin "1") (pinfunction "1_1") (pintype "passive"))
      (node (ref "U3") (pin "57") (pinfunction "CP_57") (pintype "output"))
    )
    (net (code "54") (name "Net-(U4-REGOUT)") (class "Default")
      (node (ref "C55") (pin "1") (pinfunction "1_1") (pintype "passive"))
      (node (ref "U4") (pin "11") (pinfunction "REGOUT_11") (pintype "passive"))
    )
    (net (code "55") (name "Net-(U5A-I)") (class "Default")
      (node (ref "R29") (pin "2") (pinfunction "2_2") (pintype "passive"))
      (node (ref "U5") (pin "2") (pinfunction "I_2") (pintype "input"))
    )
    (net (code "56") (name "Net-(U5A-O)") (class "Default")
      (node (ref "R31") (pin "1") (pinfunction "1_1") (pintype "passive"))
      (node (ref "U5") (pin "4") (pinfunction "O_4") (pintype "output"))
    )
    (net (code "57") (name "Net-(U6A-I)") (class "Default")
      (node (ref "R30") (pin "2") (pinfunction "2_2") (pintype "passive"))
      (node (ref "U6") (pin "2") (pinfunction "I_2") (pintype "input"))
    )
    (net (code "58") (name "Net-(U6A-O)") (class "Default")
      (node (ref "R32") (pin "1") (pinfunction "1_1") (pintype "passive"))
      (node (ref "U6") (pin "4") (pinfunction "O_4") (pintype "output"))
    )
    (net (code "59") (name "POWERSTEP-BUSY") (class "Default")
      (node (ref "BUSY") (pin "C") (pinfunction "C_C") (pintype "passive"))
      (node (ref "U1") (pin "39") (pinfunction "PE8_39") (pintype "bidirectional"))
      (node (ref "U3") (pin "15") (pinfunction "~{BUSY}/SYNC_15") (pintype "output"))
    )
    (net (code "60") (name "POWERSTEP-CS") (class "Default")
      (node (ref "U1") (pin "29") (pinfunction "PA4_29") (pintype "bidirectional"))
      (node (ref "U3") (pin "10") (pinfunction "~{CS}_10") (pintype "input"))
    )
    (net (code "61") (name "POWERSTEP-FLAG") (class "Default")
      (node (ref "FLAG") (pin "C") (pinfunction "C_C") (pintype "passive"))
      (node (ref "U1") (pin "38") (pinfunction "PE7_38") (pintype "bidirectional"))
      (node (ref "U3") (pin "16") (pinfunction "~{FLAG}_16") (pintype "output"))
    )
    (net (code "62") (name "POWERSTEP-SCK") (class "Default")
      (node (ref "PST-SCK") (pin "TP") (pinfunction "TP_TP") (pintype "input"))
      (node (ref "U1") (pin "30") (pinfunction "PA5_30") (pintype "bidirectional"))
      (node (ref "U3") (pin "11") (pinfunction "CK_11") (pintype "input"))
    )
    (net (code "63") (name "POWERSTEP-SDI") (class "Default")
      (node (ref "PST-SDI") (pin "TP") (pinfunction "TP_TP") (pintype "input"))
      (node (ref "U1") (pin "32") (pinfunction "PA7_32") (pintype "bidirectional"))
      (node (ref "U3") (pin "12") (pinfunction "SDI_12") (pintype "input"))
    )
    (net (code "64") (name "POWERSTEP-SDO") (class "Default")
      (node (ref "PST-SDO") (pin "TP") (pinfunction "TP_TP") (pintype "input"))
      (node (ref "U1") (pin "31") (pinfunction "PA6_31") (pintype "bidirectional"))
      (node (ref "U3") (pin "14") (pinfunction "SDO_14") (pintype "output"))
    )
    (net (code "65") (name "POWERSTEP-STBY") (class "Default")
      (node (ref "R1") (pin "1") (pinfunction "1_1") (pintype "passive"))
      (node (ref "U1") (pin "40") (pinfunction "PE9_40") (pintype "bidirectional"))
      (node (ref "U3") (pin "19") (pinfunction "~{STBY}/~{RESET}_19") (pintype "input"))
    )
    (net (code "66") (name "POWERSTEP-STCK") (class "Default")
      (node (ref "U1") (pin "26") (pinfunction "PA3_26") (pintype "bidirectional"))
      (node (ref "U3") (pin "17") (pinfunction "STCK_17") (pintype "input"))
    )
    (net (code "67") (name "POWERSTEP-SW") (class "Default")
      (node (ref "U1") (pin "41") (pinfunction "PE10_41") (pintype "bidirectional"))
      (node (ref "U3") (pin "18") (pinfunction "SW_18") (pintype "input"))
    )
    (net (code "68") (name "RX") (class "Default")
      (node (ref "R30") (pin "1") (pinfunction "1_1") (pintype "passive"))
      (node (ref "RX") (pin "TP") (pinfunction "TP_TP") (pintype "input"))
    )
    (net (code "69") (name "SENSEA") (class "Default")
      (node (ref "R4") (pin "2") (pinfunction "2_2") (pintype "passive"))
      (node (ref "U3") (pin "20") (pinfunction "SENSEA_S_20") (pintype "input"))
      (node (ref "U3") (pin "34") (pinfunction "SENSEA_P_34") (pintype "input"))
      (node (ref "U3") (pin "39") (pinfunction "SENSEA_P_39") (pintype "input"))
    )
    (net (code "70") (name "SENSEB") (class "Default")
      (node (ref "R6") (pin "2") (pinfunction "2_2") (pintype "passive"))
      (node (ref "U3") (pin "77") (pinfunction "SENSEB_P_77") (pintype "input"))
      (node (ref "U3") (pin "82") (pinfunction "SENSEB_P_82") (pintype "input"))
      (node (ref "U3") (pin "9") (pinfunction "SENSEB_S_9") (pintype "input"))
    )
    (net (code "71") (name "SYS-JTCK-SWCLK") (class "Default")
      (node (ref "SWCLK") (pin "TP") (pinfunction "TP_TP") (pintype "input"))
      (node (ref "U1") (pin "76") (pinfunction "PA14_76") (pintype "bidirectional"))
    )
    (net (code "72") (name "SYS-JTDI") (class "Default")
      (node (ref "JTDI") (pin "TP") (pinfunction "TP_TP") (pintype "input"))
      (node (ref "U1") (pin "77") (pinfunction "PA15_77") (pintype "bidirectional"))
    )
    (net (code "73") (name "SYS-JTDO-SWO") (class "Default")
      (node (ref "JTDO") (pin "TP") (pinfunction "TP_TP") (pintype "input"))
      (node (ref "U1") (pin "89") (pinfunction "PB3_89") (pintype "bidirectional"))
    )
    (net (code "74") (name "SYS-JTMS-SWDIO") (class "Default")
      (node (ref "SWDIO") (pin "TP") (pinfunction "TP_TP") (pintype "input"))
      (node (ref "U1") (pin "72") (pinfunction "PA13_72") (pintype "bidirectional"))
    )
    (net (code "75") (name "SYS-JTRST") (class "Default")
      (node (ref "JTRST") (pin "TP") (pinfunction "TP_TP") (pintype "input"))
      (node (ref "U1") (pin "90") (pinfunction "PB4_90") (pintype "bidirectional"))
    )
    (net (code "76") (name "TX") (class "Default")
      (node (ref "R31") (pin "2") (pinfunction "2_2") (pintype "passive"))
      (node (ref "TX") (pin "TP") (pinfunction "TP_TP") (pintype "input"))
    )
    (net (code "77") (name "UART-RX") (class "Default")
      (node (ref "R32") (pin "2") (pinfunction "2_2") (pintype "passive"))
      (node (ref "U1") (pin "64") (pinfunction "PC7_64") (pintype "bidirectional"))
    )
    (net (code "78") (name "UART-RX-ENABLE") (class "Default")
      (node (ref "U1") (pin "60") (pinfunction "PD13_60") (pintype "bidirectional"))
      (node (ref "U6") (pin "1") (pinfunction "OE_1") (pintype "input"))
    )
    (net (code "79") (name "UART-TX") (class "Default")
      (node (ref "R29") (pin "1") (pinfunction "1_1") (pintype "passive"))
      (node (ref "U1") (pin "63") (pinfunction "PC6_63") (pintype "bidirectional"))
    )
    (net (code "80") (name "UART-TX-ENABLE") (class "Default")
      (node (ref "U1") (pin "58") (pinfunction "PD11_58") (pintype "bidirectional"))
      (node (ref "U5") (pin "1") (pinfunction "OE_1") (pintype "input"))
    )
    (net (code "81") (name "USB-D+") (class "Default")
      (node (ref "R19") (pin "2") (pinfunction "2_2") (pintype "passive"))
      (node (ref "U1") (pin "71") (pinfunction "PA12_71") (pintype "bidirectional"))
    )
    (net (code "82") (name "USB-D-") (class "Default")
      (node (ref "R20") (pin "2") (pinfunction "2_2") (pintype "passive"))
      (node (ref "U1") (pin "70") (pinfunction "PA11_70") (pintype "bidirectional"))
    )
    (net (code "83") (name "USB-ID") (class "Default")
      (node (ref "D2") (pin "1") (pinfunction "1_1") (pintype "bidirectional"))
      (node (ref "U1") (pin "69") (pinfunction "PA10_69") (pintype "bidirectional"))
    )
    (net (code "84") (name "USB-VBUS") (class "Default")
      (node (ref "R21") (pin "2") (pinfunction "2_2") (pintype "passive"))
      (node (ref "R22") (pin "1") (pinfunction "1_1") (pintype "passive"))
      (node (ref "U1") (pin "68") (pinfunction "PA9_68") (pintype "bidirectional"))
    )
    (net (code "85") (name "VCAP_1") (class "Default")
      (node (ref "C51") (pin "1") (pinfunction "1_1") (pintype "passive"))
      (node (ref "U1") (pin "48") (pinfunction "VCAP_1_48") (pintype "power_in"))
    )
    (net (code "86") (name "VCAP_2") (class "Default")
      (node (ref "C54") (pin "1") (pinfunction "1_1") (pintype "passive"))
      (node (ref "U1") (pin "73") (pinfunction "VCAP_2_73") (pintype "power_in"))
    )
    (net (code "87") (name "VCC") (class "Default")
      (node (ref "C10") (pin "+") (pinfunction "+_+") (pintype "passive"))
      (node (ref "C11") (pin "+") (pinfunction "+_+") (pintype "passive"))
      (node (ref "C13") (pin "1") (pinfunction "1_1") (pintype "passive"))
      (node (ref "C18") (pin "1") (pinfunction "1_1") (pintype "passive"))
      (node (ref "C20") (pin "1") (pinfunction "1_1") (pintype "passive"))
      (node (ref "C24") (pin "1") (pinfunction "1_1") (pintype "passive"))
      (node (ref "C7") (pin "1") (pinfunction "1_1") (pintype "passive"))
      (node (ref "C8") (pin "1") (pinfunction "1_1") (pintype "passive"))
      (node (ref "C9") (pin "1") (pinfunction "1_1") (pintype "passive"))
      (node (ref "D3") (pin "1") (pinfunction "A2_1") (pintype "bidirectional"))
      (node (ref "JP1") (pin "1") (pinfunction "1_1") (pintype "passive"))
      (node (ref "PS1") (pin "11") (pinfunction "VCC_3_11") (pintype "bidirectional"))
      (node (ref "PS1") (pin "2") (pinfunction "VCC_1_2") (pintype "bidirectional"))
      (node (ref "PS1") (pin "3") (pinfunction "VCC_2_3") (pintype "bidirectional"))
      (node (ref "R15") (pin "2") (pinfunction "2_2") (pintype "passive"))
      (node (ref "U3") (pin "1") (pinfunction "VS_1") (pintype "passive"))
      (node (ref "U3") (pin "23") (pinfunction "VS_23") (pintype "passive"))
      (node (ref "U3") (pin "43") (pinfunction "VS_43") (pintype "passive"))
      (node (ref "U3") (pin "55") (pinfunction "VS_55") (pintype "passive"))
      (node (ref "U3") (pin "66") (pinfunction "VS_66") (pintype "passive"))
    )
    (net (code "88") (name "VCC-POWERSTEP") (class "Default")
      (node (ref "C15") (pin "1") (pinfunction "1_1") (pintype "passive"))
      (node (ref "JP3") (pin "1") (pinfunction "1_1") (pintype "passive"))
      (node (ref "U3") (pin "58") (pinfunction "VCC_58") (pintype "power_in"))
    )
    (net (code "89") (name "VCCREG") (class "Default")
      (node (ref "C25") (pin "1") (pinfunction "1_1") (pintype "passive"))
      (node (ref "JP3") (pin "2") (pinfunction "2_2") (pintype "passive"))
      (node (ref "U3") (pin "60") (pinfunction "VCCREG_60") (pintype "power_in"))
    )
    (net (code "90") (name "VDD") (class "Default")
      (node (ref "C17") (pin "1") (pinfunction "1_1") (pintype "passive"))
      (node (ref "JP2") (pin "2") (pinfunction "2_2") (pintype "passive"))
      (node (ref "R26") (pin "2") (pinfunction "2_2") (pintype "passive"))
      (node (ref "R28") (pin "2") (pinfunction "2_2") (pintype "passive"))
      (node (ref "U3") (pin "13") (pinfunction "VDDIO_13") (pintype "power_in"))
    )
    (net (code "91") (name "VDDA") (class "Default")
      (node (ref "C46") (pin "1") (pinfunction "1_1") (pintype "passive"))
      (node (ref "C48") (pin "1") (pinfunction "1_1") (pintype "passive"))
      (node (ref "R12") (pin "2") (pinfunction "2_2") (pintype "passive"))
      (node (ref "U1") (pin "22") (pinfunction "VDDA_22") (pintype "power_in"))
    )
    (net (code "92") (name "VREG") (class "Default")
      (node (ref "C16") (pin "1") (pinfunction "1_1") (pintype "passive"))
      (node (ref "C22") (pin "1") (pinfunction "1_1") (pintype "passive"))
      (node (ref "JP2") (pin "1") (pinfunction "1_1") (pintype "passive"))
      (node (ref "U3") (pin "62") (pinfunction "VREG_62") (pintype "power_in"))
    )
    (net (code "93") (name "VSREG") (class "Default")
      (node (ref "C14") (pin "1") (pinfunction "1_1") (pintype "passive"))
      (node (ref "JP1") (pin "2") (pinfunction "2_2") (pintype "passive"))
      (node (ref "U3") (pin "61") (pinfunction "VSREG_61") (pintype "power_in"))
    )
    (net (code "94") (name "VSW") (class "Default")
      (node (ref "C26") (pin "1") (pinfunction "1_1") (pintype "passive"))
      (node (ref "D1") (pin "1") (pinfunction "K_1") (pintype "passive"))
      (node (ref "L1") (pin "1") (pinfunction "1_1") (pintype "passive"))
      (node (ref "PS1") (pin "1") (pinfunction "VSW_1_1") (pintype "bidirectional"))
      (node (ref "PS1") (pin "12") (pinfunction "VSW_2_12") (pintype "bidirectional"))
      (node (ref "PS1") (pin "13") (pinfunction "VSW_3_13") (pintype "bidirectional"))
      (node (ref "PS1") (pin "16") (pinfunction "VSW_4_16") (pintype "bidirectional"))
    )
    (net (code "95") (name "unconnected-(PS1-EN{slash}SYNC-Pad9)") (class "Default")
      (node (ref "PS1") (pin "9") (pinfunction "EN/SYNC_9") (pintype "bidirectional"))
    )
    (net (code "96") (name "unconnected-(PS1-NC_1-Pad6)") (class "Default")
      (node (ref "PS1") (pin "6") (pinfunction "NC_1_6") (pintype "bidirectional"))
    )
    (net (code "97") (name "unconnected-(PS1-NC_2-Pad7)") (class "Default")
      (node (ref "PS1") (pin "7") (pinfunction "NC_2_7") (pintype "bidirectional"))
    )
    (net (code "98") (name "unconnected-(PS1-PG-Pad8)") (class "Default")
      (node (ref "PS1") (pin "8") (pinfunction "PG_8") (pintype "bidirectional"))
    )
    (net (code "99") (name "unconnected-(PS2-NC-Pad4)") (class "Default")
      (node (ref "PS2") (pin "4") (pinfunction "NC_4") (pintype "no_connect"))
    )
    (net (code "100") (name "unconnected-(PS3-NC-Pad4)") (class "Default")
      (node (ref "PS3") (pin "4") (pinfunction "NC_4") (pintype "no_connect"))
    )
    (net (code "101") (name "unconnected-(U1-BOOT0-Pad94)") (class "Default")
      (node (ref "U1") (pin "94") (pinfunction "BOOT0_94") (pintype "input"))
    )
    (net (code "102") (name "unconnected-(U1-PA0-Pad23)") (class "Default")
      (node (ref "U1") (pin "23") (pinfunction "PA0_23") (pintype "bidirectional"))
    )
    (net (code "103") (name "unconnected-(U1-PA1-Pad24)") (class "Default")
      (node (ref "U1") (pin "24") (pinfunction "PA1_24") (pintype "bidirectional"))
    )
    (net (code "104") (name "unconnected-(U1-PA2-Pad25)") (class "Default")
      (node (ref "U1") (pin "25") (pinfunction "PA2_25") (pintype "bidirectional"))
    )
    (net (code "105") (name "unconnected-(U1-PA8-Pad67)") (class "Default")
      (node (ref "U1") (pin "67") (pinfunction "PA8_67") (pintype "bidirectional"))
    )
    (net (code "106") (name "unconnected-(U1-PB1-Pad36)") (class "Default")
      (node (ref "U1") (pin "36") (pinfunction "PB1_36") (pintype "bidirectional"))
    )
    (net (code "107") (name "unconnected-(U1-PB2-Pad37)") (class "Default")
      (node (ref "U1") (pin "37") (pinfunction "PB2_37") (pintype "bidirectional"))
    )
    (net (code "108") (name "unconnected-(U1-PB7-Pad93)") (class "Default")
      (node (ref "U1") (pin "93") (pinfunction "PB7_93") (pintype "bidirectional"))
    )
    (net (code "109") (name "unconnected-(U1-PB8-Pad95)") (class "Default")
      (node (ref "U1") (pin "95") (pinfunction "PB8_95") (pintype "bidirectional"))
    )
    (net (code "110") (name "unconnected-(U1-PB9-Pad96)") (class "Default")
      (node (ref "U1") (pin "96") (pinfunction "PB9_96") (pintype "bidirectional"))
    )
    (net (code "111") (name "unconnected-(U1-PB10-Pad47)") (class "Default")
      (node (ref "U1") (pin "47") (pinfunction "PB10_47") (pintype "bidirectional"))
    )
    (net (code "112") (name "unconnected-(U1-PC3-Pad18)") (class "Default")
      (node (ref "U1") (pin "18") (pinfunction "PC3_18") (pintype "bidirectional"))
    )
    (net (code "113") (name "unconnected-(U1-PC13-Pad7)") (class "Default")
      (node (ref "U1") (pin "7") (pinfunction "PC13_7") (pintype "bidirectional"))
    )
    (net (code "114") (name "unconnected-(U1-PD5-Pad86)") (class "Default")
      (node (ref "U1") (pin "86") (pinfunction "PD5_86") (pintype "bidirectional"))
    )
    (net (code "115") (name "unconnected-(U1-PD6-Pad87)") (class "Default")
      (node (ref "U1") (pin "87") (pinfunction "PD6_87") (pintype "bidirectional"))
    )
    (net (code "116") (name "unconnected-(U1-PD7-Pad88)") (class "Default")
      (node (ref "U1") (pin "88") (pinfunction "PD7_88") (pintype "bidirectional"))
    )
    (net (code "117") (name "unconnected-(U1-PD9-Pad56)") (class "Default")
      (node (ref "U1") (pin "56") (pinfunction "PD9_56") (pintype "bidirectional"))
    )
    (net (code "118") (name "unconnected-(U1-PD10-Pad57)") (class "Default")
      (node (ref "U1") (pin "57") (pinfunction "PD10_57") (pintype "bidirectional"))
    )
    (net (code "119") (name "unconnected-(U1-PD12-Pad59)") (class "Default")
      (node (ref "U1") (pin "59") (pinfunction "PD12_59") (pintype "bidirectional"))
    )
    (net (code "120") (name "unconnected-(U1-PD14-Pad61)") (class "Default")
      (node (ref "U1") (pin "61") (pinfunction "PD14_61") (pintype "bidirectional"))
    )
    (net (code "121") (name "unconnected-(U1-PD15-Pad62)") (class "Default")
      (node (ref "U1") (pin "62") (pinfunction "PD15_62") (pintype "bidirectional"))
    )
    (net (code "122") (name "unconnected-(U1-PE0-Pad97)") (class "Default")
      (node (ref "U1") (pin "97") (pinfunction "PE0_97") (pintype "bidirectional"))
    )
    (net (code "123") (name "unconnected-(U1-PE1-Pad98)") (class "Default")
      (node (ref "U1") (pin "98") (pinfunction "PE1_98") (pintype "bidirectional"))
    )
    (net (code "124") (name "unconnected-(U1-PE2-Pad1)") (class "Default")
      (node (ref "U1") (pin "1") (pinfunction "PE2_1") (pintype "bidirectional"))
    )
    (net (code "125") (name "unconnected-(U1-PE3-Pad2)") (class "Default")
      (node (ref "U1") (pin "2") (pinfunction "PE3_2") (pintype "bidirectional"))
    )
    (net (code "126") (name "unconnected-(U1-PE4-Pad3)") (class "Default")
      (node (ref "U1") (pin "3") (pinfunction "PE4_3") (pintype "bidirectional"))
    )
    (net (code "127") (name "unconnected-(U1-PE5-Pad4)") (class "Default")
      (node (ref "U1") (pin "4") (pinfunction "PE5_4") (pintype "bidirectional"))
    )
    (net (code "128") (name "unconnected-(U1-PE6-Pad5)") (class "Default")
      (node (ref "U1") (pin "5") (pinfunction "PE6_5") (pintype "bidirectional"))
    )
    (net (code "129") (name "unconnected-(U1-PE11-Pad42)") (class "Default")
      (node (ref "U1") (pin "42") (pinfunction "PE11_42") (pintype "bidirectional"))
    )
    (net (code "130") (name "unconnected-(U1-PE12-Pad43)") (class "Default")
      (node (ref "U1") (pin "43") (pinfunction "PE12_43") (pintype "bidirectional"))
    )
    (net (code "131") (name "unconnected-(U1-PE13-Pad44)") (class "Default")
      (node (ref "U1") (pin "44") (pinfunction "PE13_44") (pintype "bidirectional"))
    )
    (net (code "132") (name "unconnected-(U1-PE15-Pad46)") (class "Default")
      (node (ref "U1") (pin "46") (pinfunction "PE15_46") (pintype "bidirectional"))
    )
    (net (code "133") (name "unconnected-(U2-A-Pad9)") (class "Default")
      (node (ref "U2") (pin "9") (pinfunction "A_9") (pintype "output"))
    )
    (net (code "134") (name "unconnected-(U2-B-Pad8)") (class "Default")
      (node (ref "U2") (pin "8") (pinfunction "B_8") (pintype "output"))
    )
    (net (code "135") (name "unconnected-(U2-I-Pad7)") (class "Default")
      (node (ref "U2") (pin "7") (pinfunction "I_7") (pintype "output"))
    )
    (net (code "136") (name "unconnected-(U2-NC1-Pad1)") (class "Default")
      (node (ref "U2") (pin "1") (pinfunction "NC1_1") (pintype "no_connect"))
    )
    (net (code "137") (name "unconnected-(U2-NC2-Pad2)") (class "Default")
      (node (ref "U2") (pin "2") (pinfunction "NC2_2") (pintype "no_connect"))
    )
    (net (code "138") (name "unconnected-(U2-NC3-Pad3)") (class "Default")
      (node (ref "U2") (pin "3") (pinfunction "NC3_3") (pintype "no_connect"))
    )
    (net (code "139") (name "unconnected-(U2-NC4-Pad4)") (class "Default")
      (node (ref "U2") (pin "4") (pinfunction "NC4_4") (pintype "no_connect"))
    )
    (net (code "140") (name "unconnected-(U2-NC5-Pad5)") (class "Default")
      (node (ref "U2") (pin "5") (pinfunction "NC5_5") (pintype "no_connect"))
    )
    (net (code "141") (name "unconnected-(U2-NC6-Pad6)") (class "Default")
      (node (ref "U2") (pin "6") (pinfunction "NC6_6") (pintype "no_connect"))
    )
    (net (code "142") (name "unconnected-(U2-NC15-Pad15)") (class "Default")
      (node (ref "U2") (pin "15") (pinfunction "NC15_15") (pintype "no_connect"))
    )
    (net (code "143") (name "unconnected-(U2-NC16-Pad16)") (class "Default")
      (node (ref "U2") (pin "16") (pinfunction "NC16_16") (pintype "no_connect"))
    )
    (net (code "144") (name "unconnected-(U2-NC17-Pad17)") (class "Default")
      (node (ref "U2") (pin "17") (pinfunction "NC17_17") (pintype "no_connect"))
    )
    (net (code "145") (name "unconnected-(U2-NC18-Pad18)") (class "Default")
      (node (ref "U2") (pin "18") (pinfunction "NC18_18") (pintype "no_connect"))
    )
    (net (code "146") (name "unconnected-(U2-U-Pad22)") (class "Default")
      (node (ref "U2") (pin "22") (pinfunction "U_22") (pintype "output"))
    )
    (net (code "147") (name "unconnected-(U2-V-Pad23)") (class "Default")
      (node (ref "U2") (pin "23") (pinfunction "V_23") (pintype "output"))
    )
    (net (code "148") (name "unconnected-(U2-W{slash}PWM-Pad24)") (class "Default")
      (node (ref "U2") (pin "24") (pinfunction "W/PWM_24") (pintype "output"))
    )
    (net (code "149") (name "unconnected-(U3-ADCIN-Pad54)") (class "Default")
      (node (ref "U3") (pin "54") (pinfunction "ADCIN_54") (pintype "input"))
    )
    (net (code "150") (name "unconnected-(U3-OSCIN-Pad63)") (class "Default")
      (node (ref "U3") (pin "63") (pinfunction "OSCIN_63") (pintype "input"))
    )
    (net (code "151") (name "unconnected-(U3-OSCOUT-Pad64)") (class "Default")
      (node (ref "U3") (pin "64") (pinfunction "OSCOUT_64") (pintype "output"))
    )
    (net (code "152") (name "unconnected-(U4-FSYNC{slash}NC-Pad10)") (class "Default")
      (node (ref "U4") (pin "10") (pinfunction "FSYNC/NC_10") (pintype "input"))
    )
  )
)
